# prototype_dual_channel.net
KiCad netlist of a schematic drawn in Altium Designer
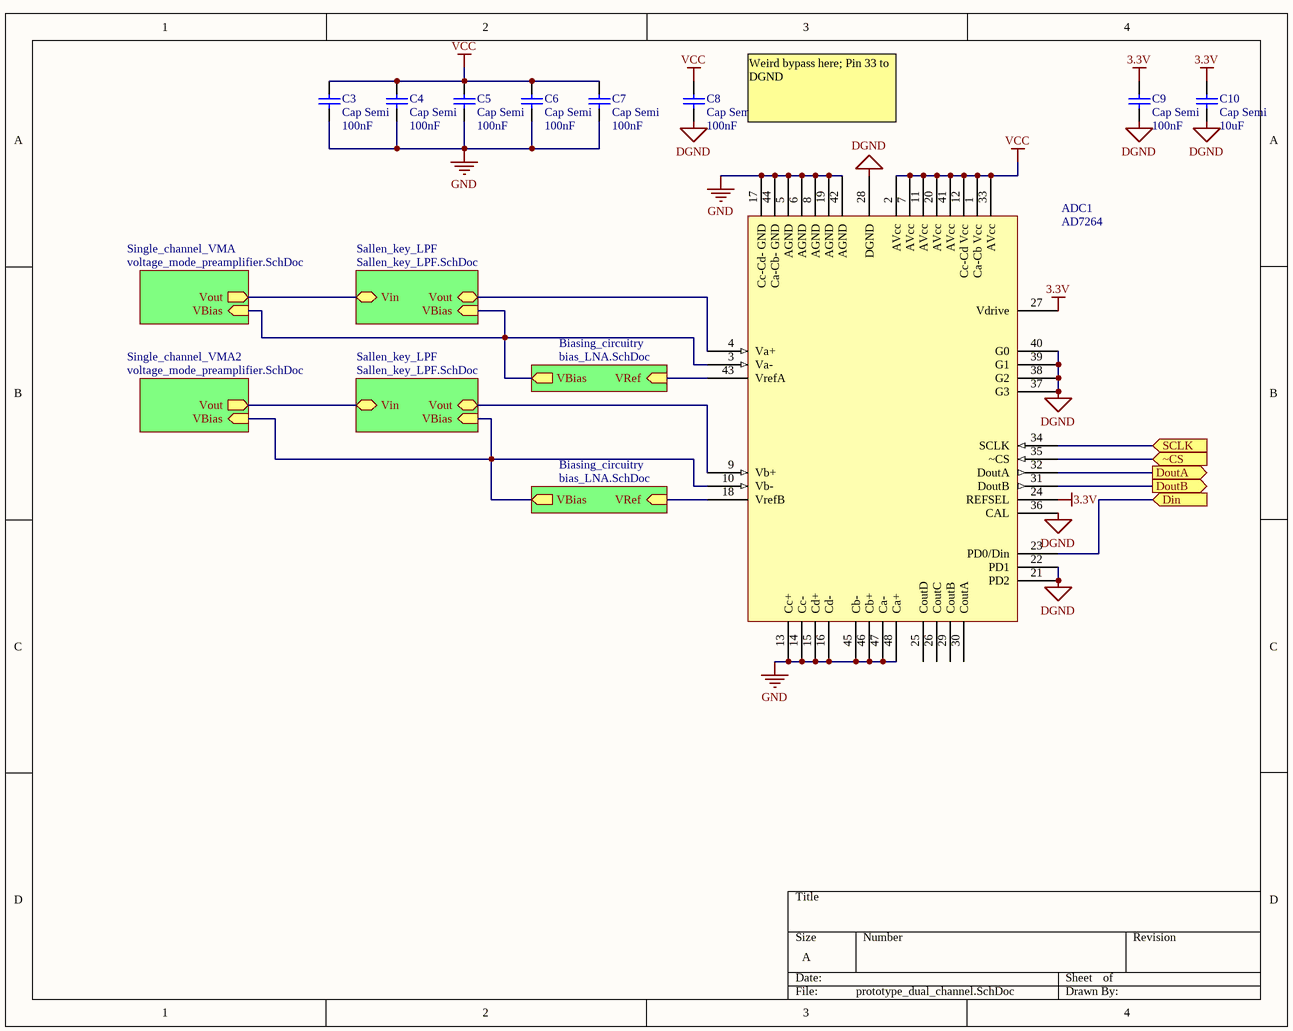
[diagram p0: prototype_dual_channel.SchDoc]

(export (version "E")
  (design (tool "Eeschema 10.0.6"))
  (components
    (comp (ref "ADC1")
      (value "AD7264")
      (footprint "QFP_Thin_Sq_50P_Side_N:TSQFP50P900X900-48N")
      (description "AD7264 - 14 bit 1MSPS 2 channel ADC")
      (libsource (lib "Sonar_board") (part "AD7264"))
    )
    (comp (ref "C3")
      (value "Cap Semi")
      (footprint "C0805")
      (description "Capacitor (Semiconductor SIM Model)")
      (fields (field (name "ALTIUM_VALUE") "100nF") (field (name "PUBLISHER") "Altium Limited"))
      (libsource (lib "Miscellaneous Devices") (part "Cap Semi"))
    )
    (comp (ref "C4")
      (value "Cap Semi")
      (footprint "C0805")
      (description "Capacitor (Semiconductor SIM Model)")
      (fields (field (name "ALTIUM_VALUE") "100nF") (field (name "PUBLISHER") "Altium Limited"))
      (libsource (lib "Miscellaneous Devices") (part "Cap Semi"))
    )
    (comp (ref "C5")
      (value "Cap Semi")
      (footprint "C0805")
      (description "Capacitor (Semiconductor SIM Model)")
      (fields (field (name "ALTIUM_VALUE") "100nF") (field (name "PUBLISHER") "Altium Limited"))
      (libsource (lib "Miscellaneous Devices") (part "Cap Semi"))
    )
    (comp (ref "C6")
      (value "Cap Semi")
      (footprint "C0805")
      (description "Capacitor (Semiconductor SIM Model)")
      (fields (field (name "ALTIUM_VALUE") "100nF") (field (name "PUBLISHER") "Altium Limited"))
      (libsource (lib "Miscellaneous Devices") (part "Cap Semi"))
    )
    (comp (ref "C7")
      (value "Cap Semi")
      (footprint "C0805")
      (description "Capacitor (Semiconductor SIM Model)")
      (fields (field (name "ALTIUM_VALUE") "100nF") (field (name "PUBLISHER") "Altium Limited"))
      (libsource (lib "Miscellaneous Devices") (part "Cap Semi"))
    )
    (comp (ref "C8")
      (value "Cap Semi")
      (footprint "C0805")
      (description "Capacitor (Semiconductor SIM Model)")
      (fields (field (name "ALTIUM_VALUE") "100nF") (field (name "PUBLISHER") "Altium Limited"))
      (libsource (lib "Miscellaneous Devices") (part "Cap Semi"))
    )
    (comp (ref "C9")
      (value "Cap Semi")
      (footprint "C0805")
      (description "Capacitor (Semiconductor SIM Model)")
      (fields (field (name "ALTIUM_VALUE") "100nF") (field (name "PUBLISHER") "Altium Limited"))
      (libsource (lib "Miscellaneous Devices") (part "Cap Semi"))
    )
    (comp (ref "C10")
      (value "Cap Semi")
      (footprint "C0805")
      (description "Capacitor (Semiconductor SIM Model)")
      (fields (field (name "ALTIUM_VALUE") "10uF") (field (name "PUBLISHER") "Altium Limited"))
      (libsource (lib "Miscellaneous Devices") (part "Cap Semi"))
    )
  )
  (nets
    (net (code "1") (name "/Din") (class "Default")
      (node (ref "ADC1") (pin "23") (pinfunction "PD0/Din_23") (pintype "passive"))
    )
    (net (code "2") (name "/DoutA") (class "Default")
      (node (ref "ADC1") (pin "32") (pinfunction "DoutA_32") (pintype "output"))
    )
    (net (code "3") (name "/DoutB") (class "Default")
      (node (ref "ADC1") (pin "31") (pinfunction "DoutB_31") (pintype "output"))
    )
    (net (code "4") (name "/SCLK") (class "Default")
      (node (ref "ADC1") (pin "34") (pinfunction "SCLK_34") (pintype "input"))
    )
    (net (code "5") (name "/VBias") (class "Default")
      (node (ref "ADC1") (pin "10") (pinfunction "Vb-_10") (pintype "input"))
    )
    (net (code "6") (name "/VBias_1") (class "Default")
      (node (ref "ADC1") (pin "3") (pinfunction "Va-_3") (pintype "input"))
    )
    (net (code "7") (name "/VRef") (class "Default")
      (node (ref "ADC1") (pin "43") (pinfunction "VrefA_43") (pintype "passive"))
    )
    (net (code "8") (name "/VRef_1") (class "Default")
      (node (ref "ADC1") (pin "18") (pinfunction "VrefB_18") (pintype "passive"))
    )
    (net (code "10") (name "/Vout_1") (class "Default")
      (node (ref "ADC1") (pin "4") (pinfunction "Va+_4") (pintype "input"))
    )
    (net (code "11") (name "/Vout_2") (class "Default")
      (node (ref "ADC1") (pin "9") (pinfunction "Vb+_9") (pintype "input"))
    )
    (net (code "13") (name "/~CS") (class "Default")
      (node (ref "ADC1") (pin "35") (pinfunction "~CS_35") (pintype "input"))
    )
    (net (code "14") (name "3.3V") (class "Default")
      (node (ref "ADC1") (pin "24") (pinfunction "REFSEL_24") (pintype "passive"))
      (node (ref "ADC1") (pin "27") (pinfunction "Vdrive_27") (pintype "passive"))
      (node (ref "C10") (pin "2") (pinfunction "2_2") (pintype "passive"))
      (node (ref "C9") (pin "2") (pinfunction "2_2") (pintype "passive"))
    )
    (net (code "15") (name "DGND") (class "Default")
      (node (ref "ADC1") (pin "21") (pinfunction "PD2_21") (pintype "passive"))
      (node (ref "ADC1") (pin "22") (pinfunction "PD1_22") (pintype "passive"))
      (node (ref "ADC1") (pin "28") (pinfunction "DGND_28") (pintype "passive"))
      (node (ref "ADC1") (pin "36") (pinfunction "CAL_36") (pintype "passive"))
      (node (ref "ADC1") (pin "37") (pinfunction "G3_37") (pintype "passive"))
      (node (ref "ADC1") (pin "38") (pinfunction "G2_38") (pintype "passive"))
      (node (ref "ADC1") (pin "39") (pinfunction "G1_39") (pintype "passive"))
      (node (ref "ADC1") (pin "40") (pinfunction "G0_40") (pintype "passive"))
      (node (ref "C10") (pin "1") (pinfunction "1_1") (pintype "passive"))
      (node (ref "C8") (pin "1") (pinfunction "1_1") (pintype "passive"))
      (node (ref "C9") (pin "1") (pinfunction "1_1") (pintype "passive"))
    )
    (net (code "16") (name "GND") (class "Default")
      (node (ref "ADC1") (pin "13") (pinfunction "Cc+_13") (pintype "passive"))
      (node (ref "ADC1") (pin "14") (pinfunction "Cc-_14") (pintype "passive"))
      (node (ref "ADC1") (pin "15") (pinfunction "Cd+_15") (pintype "passive"))
      (node (ref "ADC1") (pin "16") (pinfunction "Cd-_16") (pintype "passive"))
      (node (ref "ADC1") (pin "17") (pinfunction "Cc-Cd-_GND_17") (pintype "passive"))
      (node (ref "ADC1") (pin "19") (pinfunction "AGND_19") (pintype "passive"))
      (node (ref "ADC1") (pin "42") (pinfunction "AGND_42") (pintype "passive"))
      (node (ref "ADC1") (pin "44") (pinfunction "Ca-Cb-_GND_44") (pintype "passive"))
      (node (ref "ADC1") (pin "45") (pinfunction "Cb-_45") (pintype "passive"))
      (node (ref "ADC1") (pin "46") (pinfunction "Cb+_46") (pintype "passive"))
      (node (ref "ADC1") (pin "47") (pinfunction "Ca-_47") (pintype "passive"))
      (node (ref "ADC1") (pin "48") (pinfunction "Ca+_48") (pintype "passive"))
      (node (ref "ADC1") (pin "5") (pinfunction "AGND_5") (pintype "passive"))
      (node (ref "ADC1") (pin "6") (pinfunction "AGND_6") (pintype "passive"))
      (node (ref "ADC1") (pin "8") (pinfunction "AGND_8") (pintype "passive"))
      (node (ref "C3") (pin "1") (pinfunction "1_1") (pintype "passive"))
      (node (ref "C4") (pin "1") (pinfunction "1_1") (pintype "passive"))
      (node (ref "C5") (pin "1") (pinfunction "1_1") (pintype "passive"))
      (node (ref "C6") (pin "1") (pinfunction "1_1") (pintype "passive"))
      (node (ref "C7") (pin "1") (pinfunction "1_1") (pintype "passive"))
    )
    (net (code "17") (name "VCC") (class "Default")
      (node (ref "ADC1") (pin "1") (pinfunction "Ca-Cb_Vcc_1") (pintype "passive"))
      (node (ref "ADC1") (pin "11") (pinfunction "AVcc_11") (pintype "passive"))
      (node (ref "ADC1") (pin "12") (pinfunction "Cc-Cd_Vcc_12") (pintype "passive"))
      (node (ref "ADC1") (pin "2") (pinfunction "AVcc_2") (pintype "passive"))
      (node (ref "ADC1") (pin "20") (pinfunction "AVcc_20") (pintype "passive"))
      (node (ref "ADC1") (pin "33") (pinfunction "AVcc_33") (pintype "passive"))
      (node (ref "ADC1") (pin "41") (pinfunction "AVcc_41") (pintype "passive"))
      (node (ref "ADC1") (pin "7") (pinfunction "AVcc_7") (pintype "passive"))
      (node (ref "C3") (pin "2") (pinfunction "2_2") (pintype "passive"))
      (node (ref "C4") (pin "2") (pinfunction "2_2") (pintype "passive"))
      (node (ref "C5") (pin "2") (pinfunction "2_2") (pintype "passive"))
      (node (ref "C6") (pin "2") (pinfunction "2_2") (pintype "passive"))
      (node (ref "C7") (pin "2") (pinfunction "2_2") (pintype "passive"))
      (node (ref "C8") (pin "2") (pinfunction "2_2") (pintype "passive"))
    )
    (net (code "18") (name "unconnected-(ADC1-CoutA-Pad30)") (class "Default")
      (node (ref "ADC1") (pin "30") (pinfunction "CoutA_30") (pintype "passive"))
    )
    (net (code "19") (name "unconnected-(ADC1-CoutB-Pad29)") (class "Default")
      (node (ref "ADC1") (pin "29") (pinfunction "CoutB_29") (pintype "passive"))
    )
    (net (code "20") (name "unconnected-(ADC1-CoutC-Pad26)") (class "Default")
      (node (ref "ADC1") (pin "26") (pinfunction "CoutC_26") (pintype "passive"))
    )
    (net (code "21") (name "unconnected-(ADC1-CoutD-Pad25)") (class "Default")
      (node (ref "ADC1") (pin "25") (pinfunction "CoutD_25") (pintype "passive"))
    )
  )
)
